# Sheet1.net
KiCad netlist of a schematic drawn in Altium Designer
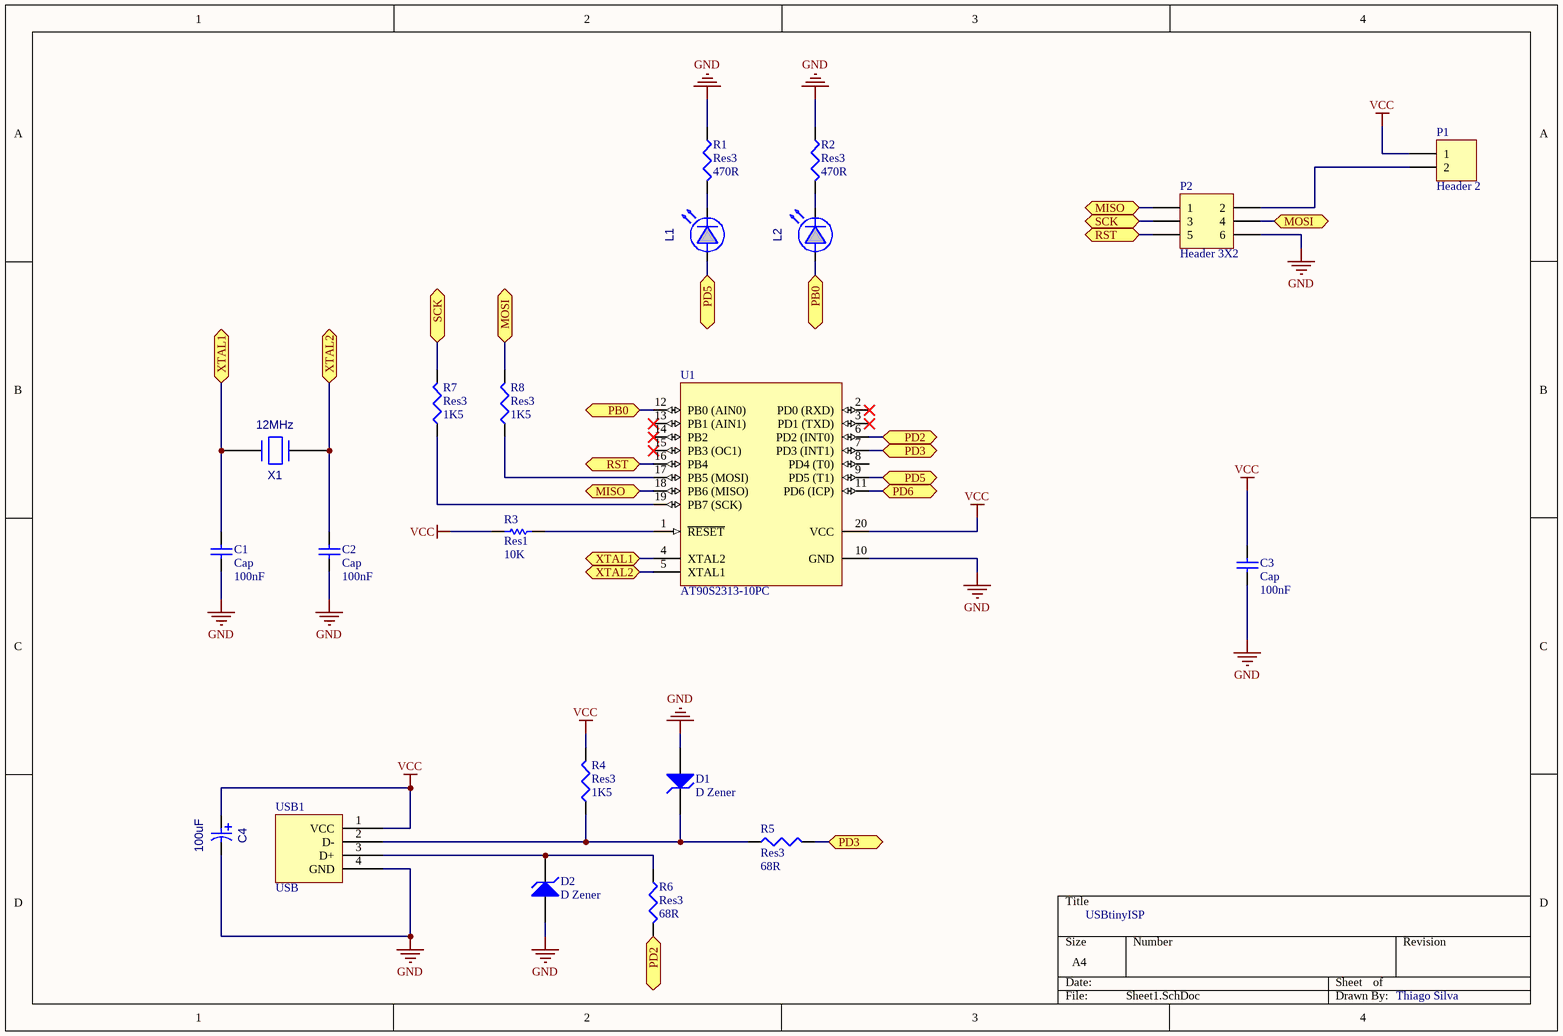
[diagram p0: Sheet1.SchDoc]

(export (version "E")
  (design (tool "Eeschema 10.0.6"))
  (components
    (comp (ref "C1")
      (value "Cap")
      (footprint "CAP CER 100nF (25V) - UP")
      (description "Capacitor")
      (fields (field (name "ALTIUM_VALUE") "100nF") (field (name "PUBLISHER") "Altium Limited"))
      (libsource (lib "Miscellaneous Devices") (part "Cap"))
    )
    (comp (ref "C2")
      (value "Cap")
      (footprint "CAP CER 100nF (25V) - UP")
      (description "Capacitor")
      (fields (field (name "ALTIUM_VALUE") "100nF") (field (name "PUBLISHER") "Altium Limited"))
      (libsource (lib "Miscellaneous Devices") (part "Cap"))
    )
    (comp (ref "C3")
      (value "Cap")
      (footprint "CAP CER 100nF (25V) - UP")
      (description "Capacitor")
      (fields (field (name "ALTIUM_VALUE") "100nF") (field (name "PUBLISHER") "Altium Limited"))
      (libsource (lib "Miscellaneous Devices") (part "Cap"))
    )
    (comp (ref "C4")
      (value "100uF")
      (footprint "CAP100RP")
      (description "CAP100RP-SC")
      (libsource (lib "SACI") (part "CAP100RP-SC"))
    )
    (comp (ref "D1")
      (value "D Zener")
      (footprint "DIODE ZENER")
      (description "Zener Diode")
      (fields (field (name "PUBLISHER") "Altium Limited"))
      (libsource (lib "Miscellaneous Devices") (part "D Zener"))
    )
    (comp (ref "D2")
      (value "D Zener")
      (footprint "DIODE ZENER")
      (description "Zener Diode")
      (fields (field (name "PUBLISHER") "Altium Limited"))
      (libsource (lib "Miscellaneous Devices") (part "D Zener"))
    )
    (comp (ref "L1") (value "LED3MM") (footprint "LED3MM") (libsource (lib "SACI") (part "LED3MM")))
    (comp (ref "L2") (value "LED3MM") (footprint "LED3MM") (libsource (lib "SACI") (part "LED3MM")))
    (comp (ref "P1")
      (value "Header 2")
      (footprint "HEADER1X2")
      (description "Header, 2-Pin")
      (fields (field (name "PUBLISHER") "Altium Limited"))
      (libsource (lib "Miscellaneous Connectors") (part "Header 2"))
    )
    (comp (ref "P2")
      (value "Header 3X2")
      (footprint "ISP")
      (description "Header, 3-Pin, Dual row")
      (fields (field (name "PUBLISHER") "Altium Limited"))
      (libsource (lib "Miscellaneous Connectors") (part "Header 3X2"))
    )
    (comp (ref "R1")
      (value "Res3")
      (footprint "AXIAL-0.4 - DOWN")
      (description "Resistor")
      (fields (field (name "ALTIUM_VALUE") "470R") (field (name "PUBLISHER") "Altium Limited"))
      (libsource (lib "Miscellaneous Devices") (part "Res3"))
    )
    (comp (ref "R2")
      (value "Res3")
      (footprint "AXIAL-0.4 - DOWN")
      (description "Resistor")
      (fields (field (name "ALTIUM_VALUE") "470R") (field (name "PUBLISHER") "Altium Limited"))
      (libsource (lib "Miscellaneous Devices") (part "Res3"))
    )
    (comp (ref "R3")
      (value "Res1")
      (footprint "AXIAL-0.4 - DOWN")
      (description "Resistor")
      (fields (field (name "ALTIUM_VALUE") "10K") (field (name "PUBLISHER") "Altium Limited"))
      (libsource (lib "Miscellaneous Devices") (part "Res1"))
    )
    (comp (ref "R4")
      (value "Res3")
      (footprint "AXIAL-0.4 - DOWN")
      (description "Resistor")
      (fields (field (name "ALTIUM_VALUE") "1K5") (field (name "PUBLISHER") "Altium Limited"))
      (libsource (lib "Miscellaneous Devices") (part "Res3"))
    )
    (comp (ref "R5")
      (value "Res3")
      (footprint "AXIAL-0.4 - DOWN")
      (description "Resistor")
      (fields (field (name "ALTIUM_VALUE") "68R") (field (name "PUBLISHER") "Altium Limited"))
      (libsource (lib "Miscellaneous Devices") (part "Res3"))
    )
    (comp (ref "R6")
      (value "Res3")
      (footprint "AXIAL-0.4 - DOWN")
      (description "Resistor")
      (fields (field (name "ALTIUM_VALUE") "68R") (field (name "PUBLISHER") "Altium Limited"))
      (libsource (lib "Miscellaneous Devices") (part "Res3"))
    )
    (comp (ref "R7")
      (value "Res3")
      (footprint "AXIAL-0.4 - DOWN")
      (description "Resistor")
      (fields (field (name "ALTIUM_VALUE") "1K5") (field (name "PUBLISHER") "Altium Limited"))
      (libsource (lib "Miscellaneous Devices") (part "Res3"))
    )
    (comp (ref "R8")
      (value "Res3")
      (footprint "AXIAL-0.4 - DOWN")
      (description "Resistor")
      (fields (field (name "ALTIUM_VALUE") "1K5") (field (name "PUBLISHER") "Altium Limited"))
      (libsource (lib "Miscellaneous Devices") (part "Res3"))
    )
    (comp (ref "U1")
      (value "AT90S2313-10PC")
      (footprint "DIP-20P")
      (description "8-Bit AVR Microcontroller with 2K Bytes of In-System Programmable Flash Memory")
      (fields (field (name "PUBLISHER") "Altium Limited"))
      (libsource (lib "Atmel Microcontroller 8-Bit AVR") (part "AT90S2313-10PC"))
    )
    (comp (ref "USB1") (value "USB") (footprint "USB2.5-2H4D") (libsource (lib "MyLibrary") (part "USB")))
    (comp (ref "X1")
      (value "12MHz")
      (footprint "CRISTAL")
      (description "CRISTAL")
      (libsource (lib "SACI") (part "CRISTAL"))
    )
  )
  (nets
    (net (code "1") (name "/MISO") (class "Default")
      (node (ref "P2") (pin "1") (pinfunction "1_1") (pintype "passive"))
      (node (ref "U1") (pin "18") (pinfunction "PB6_(MISO)_18") (pintype "bidirectional"))
    )
    (net (code "2") (name "/MOSI") (class "Default")
      (node (ref "P2") (pin "4") (pinfunction "4_4") (pintype "passive"))
      (node (ref "R8") (pin "2") (pinfunction "2_2") (pintype "passive"))
    )
    (net (code "3") (name "/PB0") (class "Default")
      (node (ref "L2") (pin "1") (pintype "passive"))
      (node (ref "U1") (pin "12") (pinfunction "PB0_(AIN0)_12") (pintype "bidirectional"))
    )
    (net (code "4") (name "/PD2") (class "Default")
      (node (ref "R6") (pin "2") (pinfunction "2_2") (pintype "passive"))
      (node (ref "U1") (pin "6") (pinfunction "PD2_(INT0)_6") (pintype "bidirectional"))
    )
    (net (code "5") (name "/PD3") (class "Default")
      (node (ref "R5") (pin "2") (pinfunction "2_2") (pintype "passive"))
      (node (ref "U1") (pin "7") (pinfunction "PD3_(INT1)_7") (pintype "bidirectional"))
    )
    (net (code "6") (name "/PD5") (class "Default")
      (node (ref "L1") (pin "1") (pintype "passive"))
      (node (ref "U1") (pin "9") (pinfunction "PD5_(T1)_9") (pintype "bidirectional"))
    )
    (net (code "7") (name "/PD6") (class "Default")
      (node (ref "U1") (pin "11") (pinfunction "PD6_(ICP)_11") (pintype "bidirectional"))
    )
    (net (code "8") (name "/RST") (class "Default")
      (node (ref "P2") (pin "5") (pinfunction "5_5") (pintype "passive"))
      (node (ref "U1") (pin "16") (pinfunction "PB4_16") (pintype "bidirectional"))
    )
    (net (code "9") (name "/SCK") (class "Default")
      (node (ref "P2") (pin "3") (pinfunction "3_3") (pintype "passive"))
      (node (ref "R7") (pin "2") (pinfunction "2_2") (pintype "passive"))
    )
    (net (code "10") (name "/XTAL1") (class "Default")
      (node (ref "C1") (pin "2") (pinfunction "2_2") (pintype "passive"))
      (node (ref "U1") (pin "4") (pinfunction "XTAL2_4") (pintype "passive"))
      (node (ref "X1") (pin "2") (pintype "passive"))
    )
    (net (code "11") (name "/XTAL2") (class "Default")
      (node (ref "C2") (pin "2") (pinfunction "2_2") (pintype "passive"))
      (node (ref "U1") (pin "5") (pinfunction "XTAL1_5") (pintype "passive"))
      (node (ref "X1") (pin "1") (pintype "passive"))
    )
    (net (code "12") (name "GND") (class "Default")
      (node (ref "C1") (pin "1") (pinfunction "1_1") (pintype "passive"))
      (node (ref "C2") (pin "1") (pinfunction "1_1") (pintype "passive"))
      (node (ref "C3") (pin "1") (pinfunction "1_1") (pintype "passive"))
      (node (ref "C4") (pin "1") (pintype "passive"))
      (node (ref "D1") (pin "1") (pinfunction "A_1") (pintype "passive"))
      (node (ref "D2") (pin "1") (pinfunction "A_1") (pintype "passive"))
      (node (ref "P2") (pin "6") (pinfunction "6_6") (pintype "passive"))
      (node (ref "R1") (pin "1") (pinfunction "1_1") (pintype "passive"))
      (node (ref "R2") (pin "1") (pinfunction "1_1") (pintype "passive"))
      (node (ref "U1") (pin "10") (pinfunction "GND_10") (pintype "power_in"))
      (node (ref "USB1") (pin "4") (pinfunction "GND_4") (pintype "passive"))
    )
    (net (code "13") (name "Net-(D1-K)") (class "Default")
      (node (ref "D1") (pin "2") (pinfunction "K_2") (pintype "passive"))
      (node (ref "R4") (pin "1") (pinfunction "1_1") (pintype "passive"))
      (node (ref "R5") (pin "1") (pinfunction "1_1") (pintype "passive"))
      (node (ref "USB1") (pin "2") (pinfunction "D-_2") (pintype "passive"))
    )
    (net (code "14") (name "Net-(D2-K)") (class "Default")
      (node (ref "D2") (pin "2") (pinfunction "K_2") (pintype "passive"))
      (node (ref "R6") (pin "1") (pinfunction "1_1") (pintype "passive"))
      (node (ref "USB1") (pin "3") (pinfunction "D+_3") (pintype "passive"))
    )
    (net (code "15") (name "Net-(L1-Pad2)") (class "Default")
      (node (ref "L1") (pin "2") (pintype "passive"))
      (node (ref "R1") (pin "2") (pinfunction "2_2") (pintype "passive"))
    )
    (net (code "16") (name "Net-(L2-Pad2)") (class "Default")
      (node (ref "L2") (pin "2") (pintype "passive"))
      (node (ref "R2") (pin "2") (pinfunction "2_2") (pintype "passive"))
    )
    (net (code "17") (name "Net-(P1-Pad2)") (class "Default")
      (node (ref "P1") (pin "2") (pinfunction "2_2") (pintype "passive"))
      (node (ref "P2") (pin "2") (pinfunction "2_2") (pintype "passive"))
    )
    (net (code "18") (name "Net-(U1-PB5_(MOSI))") (class "Default")
      (node (ref "R8") (pin "1") (pinfunction "1_1") (pintype "passive"))
      (node (ref "U1") (pin "17") (pinfunction "PB5_(MOSI)_17") (pintype "bidirectional"))
    )
    (net (code "19") (name "Net-(U1-PB7_(SCK))") (class "Default")
      (node (ref "R7") (pin "1") (pinfunction "1_1") (pintype "passive"))
      (node (ref "U1") (pin "19") (pinfunction "PB7_(SCK)_19") (pintype "bidirectional"))
    )
    (net (code "20") (name "Net-(U1-~{RESET})") (class "Default")
      (node (ref "R3") (pin "1") (pinfunction "1_1") (pintype "passive"))
      (node (ref "U1") (pin "1") (pinfunction "~{RESET}_1") (pintype "input"))
    )
    (net (code "21") (name "VCC") (class "Default")
      (node (ref "C3") (pin "2") (pinfunction "2_2") (pintype "passive"))
      (node (ref "C4") (pin "2") (pintype "passive"))
      (node (ref "P1") (pin "1") (pinfunction "1_1") (pintype "passive"))
      (node (ref "R3") (pin "2") (pinfunction "2_2") (pintype "passive"))
      (node (ref "R4") (pin "2") (pinfunction "2_2") (pintype "passive"))
      (node (ref "U1") (pin "20") (pinfunction "VCC_20") (pintype "power_in"))
      (node (ref "USB1") (pin "1") (pinfunction "VCC_1") (pintype "passive"))
    )
    (net (code "22") (name "unconnected-(U1-PB1_(AIN1)-Pad13)") (class "Default")
      (node (ref "U1") (pin "13") (pinfunction "PB1_(AIN1)_13") (pintype "bidirectional+no_connect"))
    )
    (net (code "23") (name "unconnected-(U1-PB2-Pad14)") (class "Default")
      (node (ref "U1") (pin "14") (pinfunction "PB2_14") (pintype "bidirectional+no_connect"))
    )
    (net (code "24") (name "unconnected-(U1-PB3_(OC1)-Pad15)") (class "Default")
      (node (ref "U1") (pin "15") (pinfunction "PB3_(OC1)_15") (pintype "bidirectional+no_connect"))
    )
    (net (code "25") (name "unconnected-(U1-PD0_(RXD)-Pad2)") (class "Default")
      (node (ref "U1") (pin "2") (pinfunction "PD0_(RXD)_2") (pintype "bidirectional+no_connect"))
    )
    (net (code "26") (name "unconnected-(U1-PD1_(TXD)-Pad3)") (class "Default")
      (node (ref "U1") (pin "3") (pinfunction "PD1_(TXD)_3") (pintype "bidirectional+no_connect"))
    )
    (net (code "27") (name "unconnected-(U1-PD4_(T0)-Pad8)") (class "Default")
      (node (ref "U1") (pin "8") (pinfunction "PD4_(T0)_8") (pintype "bidirectional"))
    )
  )
)
